# SilentStepStick_v12_5V.net
KiCad netlist of a schematic drawn in EAGLE
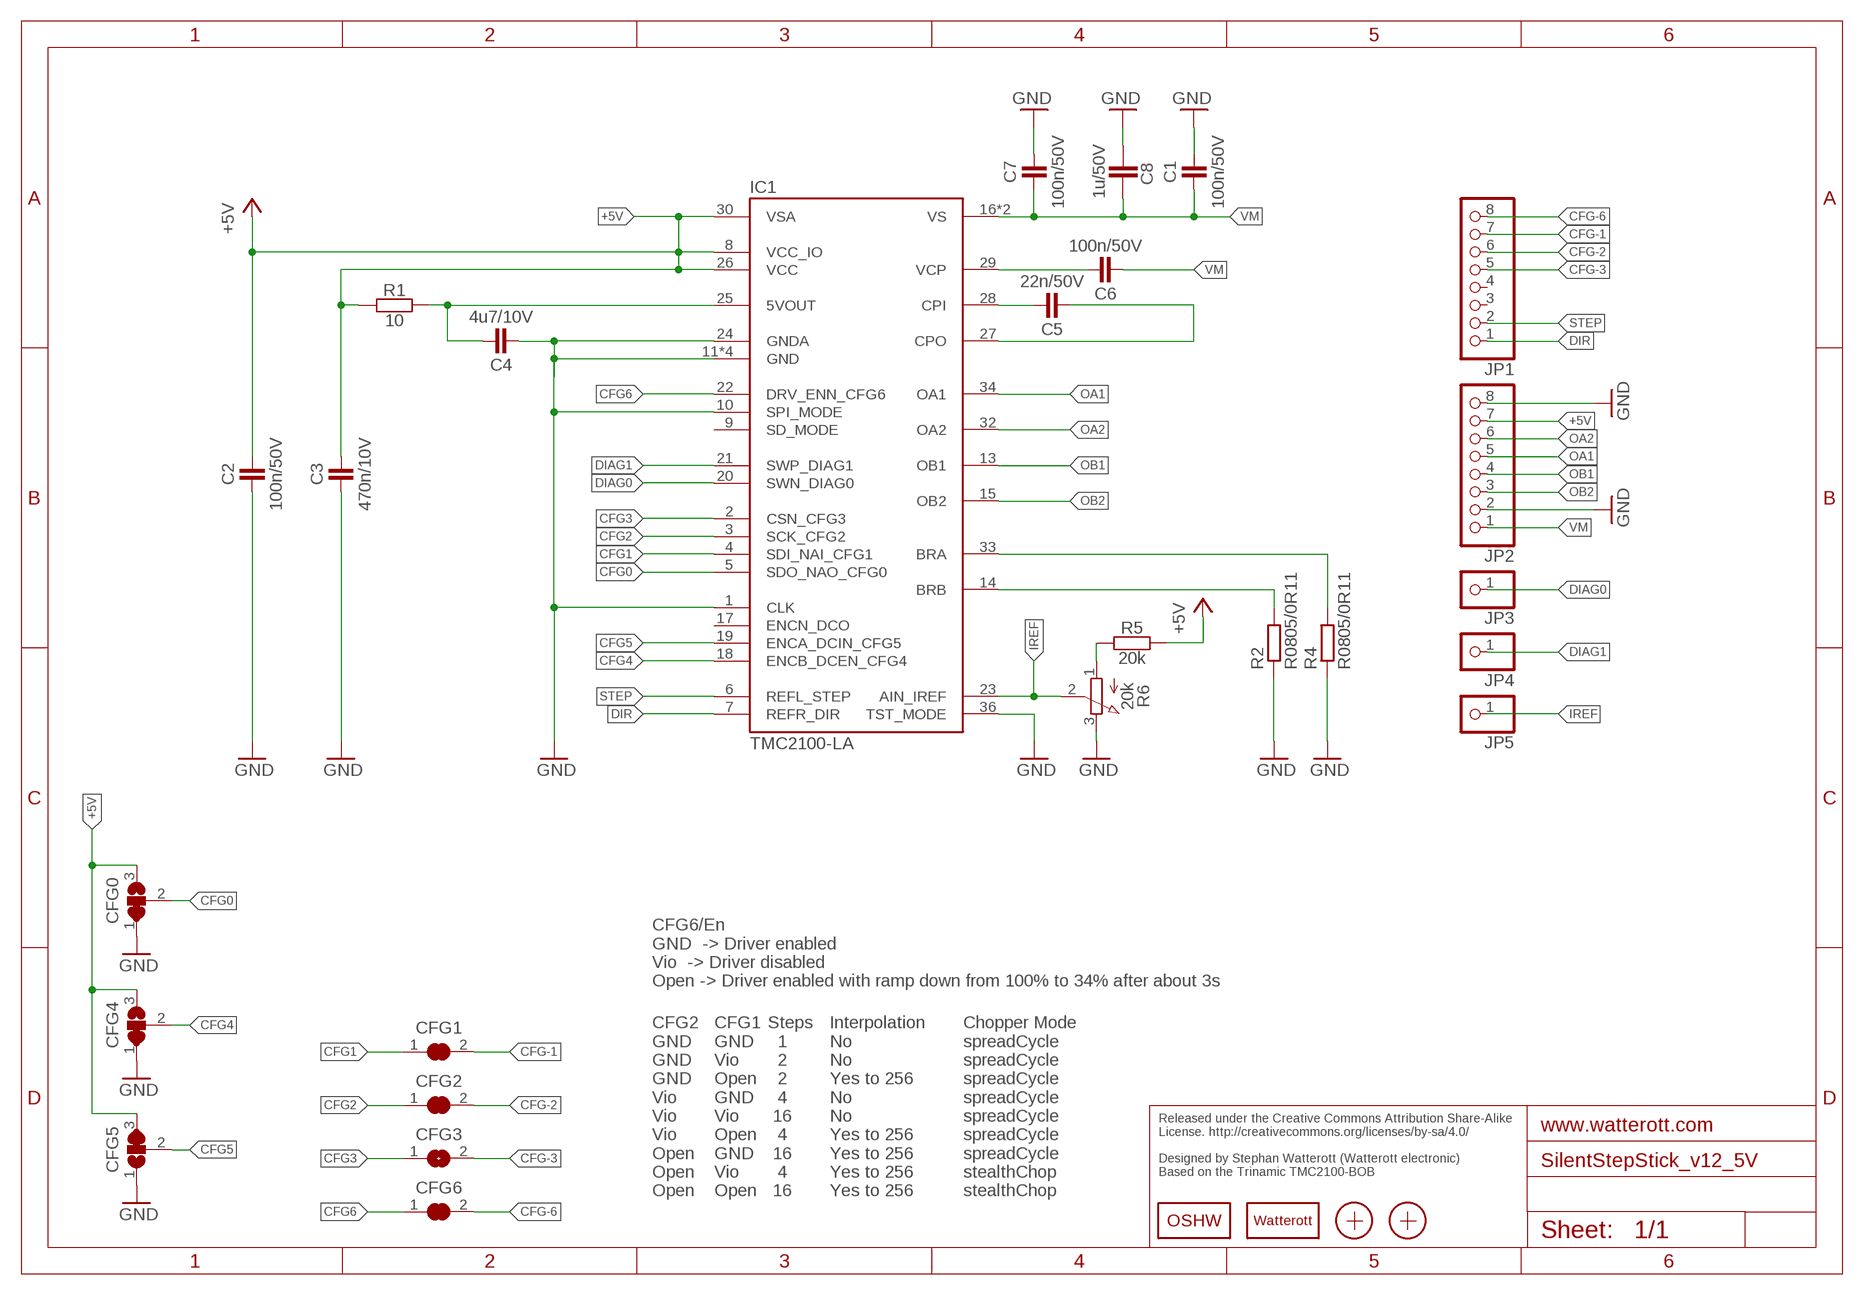
[diagram p0: schematic, sheet 1]

(export (version "E")
  (design (tool "Eeschema 10.0.6"))
  (components
    (comp (ref "C1")
      (value "100n/50V")
      (footprint "eagle-import:C0402")
      (libsource (lib "eagle-import") (part "CAPACITOR-0402"))
    )
    (comp (ref "C2")
      (value "100n/50V")
      (footprint "eagle-import:C0402")
      (libsource (lib "eagle-import") (part "CAPACITOR-0402"))
    )
    (comp (ref "C3")
      (value "470n/10V")
      (footprint "eagle-import:C0402")
      (libsource (lib "eagle-import") (part "CAPACITOR-0402"))
    )
    (comp (ref "C4")
      (value "4u7/10V")
      (footprint "eagle-import:C0402")
      (libsource (lib "eagle-import") (part "CAPACITOR-0402"))
    )
    (comp (ref "C5")
      (value "22n/50V")
      (footprint "eagle-import:C0402")
      (libsource (lib "eagle-import") (part "CAPACITOR-0402"))
    )
    (comp (ref "C6")
      (value "100n/50V")
      (footprint "eagle-import:C0402")
      (libsource (lib "eagle-import") (part "CAPACITOR-0402"))
    )
    (comp (ref "C7")
      (value "100n/50V")
      (footprint "eagle-import:C0402")
      (libsource (lib "eagle-import") (part "CAPACITOR-0402"))
    )
    (comp (ref "C8")
      (value "1u/50V")
      (footprint "eagle-import:C0603")
      (libsource (lib "eagle-import") (part "C-EUC0603"))
    )
    (comp (ref "CFG0")
      (value "JUMPER3-0201")
      (footprint "eagle-import:JUMPER3-0201")
      (libsource (lib "eagle-import") (part "JUMPER3-0201"))
    )
    (comp (ref "CFG1")
      (value "JUMPER2-0201")
      (footprint "eagle-import:JUMPER2-0201")
      (libsource (lib "eagle-import") (part "JUMPER2-0201"))
    )
    (comp (ref "CFG2")
      (value "JUMPER2-0201")
      (footprint "eagle-import:JUMPER2-0201")
      (libsource (lib "eagle-import") (part "JUMPER2-0201"))
    )
    (comp (ref "CFG3")
      (value "JUMPER2-0201")
      (footprint "eagle-import:JUMPER2-0201")
      (libsource (lib "eagle-import") (part "JUMPER2-0201"))
    )
    (comp (ref "CFG4")
      (value "JUMPER3-0201")
      (footprint "eagle-import:JUMPER3-0201")
      (libsource (lib "eagle-import") (part "JUMPER3-0201"))
    )
    (comp (ref "CFG5")
      (value "JUMPER3-0201")
      (footprint "eagle-import:JUMPER3-0201")
      (libsource (lib "eagle-import") (part "JUMPER3-0201"))
    )
    (comp (ref "CFG6")
      (value "JUMPER2-0201")
      (footprint "eagle-import:JUMPER2-0201")
      (libsource (lib "eagle-import") (part "JUMPER2-0201"))
    )
    (comp (ref "IC1")
      (value "TMC2100-LA")
      (footprint "eagle-import:QFN36-PAD")
      (libsource (lib "eagle-import") (part "TMC2100-LA"))
    )
    (comp (ref "JP1")
      (value "PINHD-1X08_2.54-S")
      (footprint "eagle-import:1X08-S")
      (libsource (lib "eagle-import") (part "PINHD-1X08_2.54-S"))
    )
    (comp (ref "JP2")
      (value "PINHD-1X08_2.54-S")
      (footprint "eagle-import:1X08-S")
      (libsource (lib "eagle-import") (part "PINHD-1X08_2.54-S"))
    )
    (comp (ref "JP3")
      (value "PINHD-1X1")
      (footprint "eagle-import:1X01")
      (libsource (lib "eagle-import") (part "PINHD-1X1"))
    )
    (comp (ref "JP4")
      (value "PINHD-1X1")
      (footprint "eagle-import:1X01")
      (libsource (lib "eagle-import") (part "PINHD-1X1"))
    )
    (comp (ref "JP5")
      (value "PINHD-1X1")
      (footprint "eagle-import:1X01")
      (libsource (lib "eagle-import") (part "PINHD-1X1"))
    )
    (comp (ref "LOGO1")
      (value "OSHW_LOGOX0070")
      (footprint "eagle-import:OSHW_6X70")
      (libsource (lib "eagle-import") (part "OSHW_LOGOX0070"))
    )
    (comp (ref "LOGO2")
      (value "LOGO-S_PLACE_M")
      (footprint "eagle-import:SPARK_TPLACE_M")
      (libsource (lib "eagle-import") (part "LOGO-S_PLACE_M"))
    )
    (comp (ref "R1")
      (value "10")
      (footprint "eagle-import:C0402")
      (libsource (lib "eagle-import") (part "RESISTOR-0402"))
    )
    (comp (ref "R2")
      (value "R0805/0R11")
      (footprint "eagle-import:M0805")
      (libsource (lib "eagle-import") (part "R-EU_M0805"))
    )
    (comp (ref "R4")
      (value "R0805/0R11")
      (footprint "eagle-import:M0805")
      (libsource (lib "eagle-import") (part "R-EU_M0805"))
    )
    (comp (ref "R5")
      (value "20k")
      (footprint "eagle-import:C0402")
      (libsource (lib "eagle-import") (part "RESISTOR-0402"))
    )
    (comp (ref "R6")
      (value "20k")
      (footprint "eagle-import:POT_EVM3R")
      (libsource (lib "eagle-import") (part "POTEVM3R"))
    )
    (comp (ref "X1")
      (value "PASSER-07")
      (footprint "eagle-import:PASSER_07MM")
      (libsource (lib "eagle-import") (part "PASSER-07"))
    )
    (comp (ref "X2")
      (value "PASSER-07")
      (footprint "eagle-import:PASSER_07MM")
      (libsource (lib "eagle-import") (part "PASSER-07"))
    )
  )
  (nets
    (net (code "1") (name "+5V") (class "Default")
      (node (ref "C2") (pin "2") (pinfunction "2_2") (pintype "passive"))
      (node (ref "C3") (pin "2") (pinfunction "2_2") (pintype "passive"))
      (node (ref "CFG0") (pin "3") (pinfunction "3_3") (pintype "passive"))
      (node (ref "CFG4") (pin "3") (pinfunction "3_3") (pintype "passive"))
      (node (ref "CFG5") (pin "3") (pinfunction "3_3") (pintype "passive"))
      (node (ref "IC1") (pin "26") (pinfunction "VCC_26") (pintype "power_in"))
      (node (ref "IC1") (pin "30") (pinfunction "VSA_30") (pintype "power_in"))
      (node (ref "IC1") (pin "8") (pinfunction "VCC_IO_8") (pintype "power_in"))
      (node (ref "JP2") (pin "7") (pinfunction "7_7") (pintype "passive"))
      (node (ref "R1") (pin "1") (pinfunction "1_1") (pintype "passive"))
      (node (ref "R5") (pin "2") (pinfunction "2_2") (pintype "passive"))
    )
    (net (code "2") (name "CFG-1") (class "Default")
      (node (ref "CFG1") (pin "2") (pinfunction "2_2") (pintype "passive"))
      (node (ref "JP1") (pin "7") (pinfunction "7_7") (pintype "passive"))
    )
    (net (code "3") (name "CFG-2") (class "Default")
      (node (ref "CFG2") (pin "2") (pinfunction "2_2") (pintype "passive"))
      (node (ref "JP1") (pin "6") (pinfunction "6_6") (pintype "passive"))
    )
    (net (code "4") (name "CFG-3") (class "Default")
      (node (ref "CFG3") (pin "2") (pinfunction "2_2") (pintype "passive"))
      (node (ref "JP1") (pin "5") (pinfunction "5_5") (pintype "passive"))
    )
    (net (code "5") (name "CFG-6") (class "Default")
      (node (ref "CFG6") (pin "2") (pinfunction "2_2") (pintype "passive"))
      (node (ref "JP1") (pin "8") (pinfunction "8_8") (pintype "passive"))
    )
    (net (code "6") (name "CFG0") (class "Default")
      (node (ref "CFG0") (pin "2") (pinfunction "2_2") (pintype "passive"))
      (node (ref "IC1") (pin "5") (pinfunction "SDO_NAO_CFG0_5") (pintype "bidirectional"))
    )
    (net (code "7") (name "CFG1") (class "Default")
      (node (ref "CFG1") (pin "1") (pinfunction "1_1") (pintype "passive"))
      (node (ref "IC1") (pin "4") (pinfunction "SDI_NAI_CFG1_4") (pintype "bidirectional"))
    )
    (net (code "8") (name "CFG2") (class "Default")
      (node (ref "CFG2") (pin "1") (pinfunction "1_1") (pintype "passive"))
      (node (ref "IC1") (pin "3") (pinfunction "SCK_CFG2_3") (pintype "bidirectional"))
    )
    (net (code "9") (name "CFG3") (class "Default")
      (node (ref "CFG3") (pin "1") (pinfunction "1_1") (pintype "passive"))
      (node (ref "IC1") (pin "2") (pinfunction "CSN_CFG3_2") (pintype "bidirectional"))
    )
    (net (code "10") (name "CFG4") (class "Default")
      (node (ref "CFG4") (pin "2") (pinfunction "2_2") (pintype "passive"))
      (node (ref "IC1") (pin "18") (pinfunction "ENCB_DCEN_CFG4_18") (pintype "bidirectional"))
    )
    (net (code "11") (name "CFG5") (class "Default")
      (node (ref "CFG5") (pin "2") (pinfunction "2_2") (pintype "passive"))
      (node (ref "IC1") (pin "19") (pinfunction "ENCA_DCIN_CFG5_19") (pintype "bidirectional"))
    )
    (net (code "12") (name "CFG6") (class "Default")
      (node (ref "CFG6") (pin "1") (pinfunction "1_1") (pintype "passive"))
      (node (ref "IC1") (pin "22") (pinfunction "DRV_ENN_CFG6_22") (pintype "bidirectional"))
    )
    (net (code "13") (name "DIAG0") (class "Default")
      (node (ref "IC1") (pin "20") (pinfunction "SWN_DIAG0_20") (pintype "bidirectional"))
      (node (ref "JP3") (pin "1") (pinfunction "1_1") (pintype "passive"))
    )
    (net (code "14") (name "DIAG1") (class "Default")
      (node (ref "IC1") (pin "21") (pinfunction "SWP_DIAG1_21") (pintype "bidirectional"))
      (node (ref "JP4") (pin "1") (pinfunction "1_1") (pintype "passive"))
    )
    (net (code "15") (name "DIR") (class "Default")
      (node (ref "IC1") (pin "7") (pinfunction "REFR_DIR_7") (pintype "bidirectional"))
      (node (ref "JP1") (pin "1") (pinfunction "1_1") (pintype "passive"))
    )
    (net (code "16") (name "GND") (class "Default")
      (node (ref "C1") (pin "2") (pinfunction "2_2") (pintype "passive"))
      (node (ref "C2") (pin "1") (pinfunction "1_1") (pintype "passive"))
      (node (ref "C3") (pin "1") (pinfunction "1_1") (pintype "passive"))
      (node (ref "C4") (pin "1") (pinfunction "1_1") (pintype "passive"))
      (node (ref "C7") (pin "2") (pinfunction "2_2") (pintype "passive"))
      (node (ref "C8") (pin "2") (pinfunction "2_2") (pintype "passive"))
      (node (ref "CFG0") (pin "1") (pinfunction "1_1") (pintype "passive"))
      (node (ref "CFG4") (pin "1") (pinfunction "1_1") (pintype "passive"))
      (node (ref "CFG5") (pin "1") (pinfunction "1_1") (pintype "passive"))
      (node (ref "IC1") (pin "1") (pinfunction "CLK_1") (pintype "bidirectional"))
      (node (ref "IC1") (pin "10") (pinfunction "SPI_MODE_10") (pintype "bidirectional"))
      (node (ref "IC1") (pin "11") (pinfunction "GND_11") (pintype "power_in"))
      (node (ref "IC1") (pin "12") (pinfunction "GND_12") (pintype "power_in"))
      (node (ref "IC1") (pin "24") (pinfunction "GNDA_24") (pintype "power_in"))
      (node (ref "IC1") (pin "35") (pinfunction "GND_35") (pintype "power_in"))
      (node (ref "IC1") (pin "36") (pinfunction "TST_MODE_36") (pintype "bidirectional"))
      (node (ref "IC1") (pin "TP") (pinfunction "GND_TP") (pintype "power_in"))
      (node (ref "JP2") (pin "2") (pinfunction "2_2") (pintype "passive"))
      (node (ref "JP2") (pin "8") (pinfunction "8_8") (pintype "passive"))
      (node (ref "R2") (pin "1") (pinfunction "1_1") (pintype "passive"))
      (node (ref "R4") (pin "1") (pinfunction "1_1") (pintype "passive"))
      (node (ref "R6") (pin "3") (pinfunction "E_3") (pintype "passive"))
    )
    (net (code "17") (name "IREF") (class "Default")
      (node (ref "IC1") (pin "23") (pinfunction "AIN_IREF_23") (pintype "passive"))
      (node (ref "JP5") (pin "1") (pinfunction "1_1") (pintype "passive"))
      (node (ref "R6") (pin "2") (pinfunction "S_2") (pintype "passive"))
    )
    (net (code "18") (name "Net-(IC1-5VOUT)") (class "Default")
      (node (ref "C4") (pin "2") (pinfunction "2_2") (pintype "passive"))
      (node (ref "IC1") (pin "25") (pinfunction "5VOUT_25") (pintype "power_in"))
      (node (ref "R1") (pin "2") (pinfunction "2_2") (pintype "passive"))
    )
    (net (code "19") (name "Net-(IC1-BRA)") (class "Default")
      (node (ref "IC1") (pin "33") (pinfunction "BRA_33") (pintype "output"))
      (node (ref "R4") (pin "2") (pinfunction "2_2") (pintype "passive"))
    )
    (net (code "20") (name "Net-(IC1-BRB)") (class "Default")
      (node (ref "IC1") (pin "14") (pinfunction "BRB_14") (pintype "output"))
      (node (ref "R2") (pin "2") (pinfunction "2_2") (pintype "passive"))
    )
    (net (code "21") (name "Net-(IC1-CPI)") (class "Default")
      (node (ref "C5") (pin "2") (pinfunction "2_2") (pintype "passive"))
      (node (ref "IC1") (pin "28") (pinfunction "CPI_28") (pintype "passive"))
    )
    (net (code "22") (name "Net-(IC1-CPO)") (class "Default")
      (node (ref "C5") (pin "1") (pinfunction "1_1") (pintype "passive"))
      (node (ref "IC1") (pin "27") (pinfunction "CPO_27") (pintype "passive"))
    )
    (net (code "23") (name "Net-(IC1-VCP)") (class "Default")
      (node (ref "C6") (pin "2") (pinfunction "2_2") (pintype "passive"))
      (node (ref "IC1") (pin "29") (pinfunction "VCP_29") (pintype "passive"))
    )
    (net (code "24") (name "Net-(R6-A)") (class "Default")
      (node (ref "R5") (pin "1") (pinfunction "1_1") (pintype "passive"))
      (node (ref "R6") (pin "1") (pinfunction "A_1") (pintype "passive"))
    )
    (net (code "25") (name "OA1") (class "Default")
      (node (ref "IC1") (pin "34") (pinfunction "OA1_34") (pintype "output"))
      (node (ref "JP2") (pin "5") (pinfunction "5_5") (pintype "passive"))
    )
    (net (code "26") (name "OA2") (class "Default")
      (node (ref "IC1") (pin "32") (pinfunction "OA2_32") (pintype "output"))
      (node (ref "JP2") (pin "6") (pinfunction "6_6") (pintype "passive"))
    )
    (net (code "27") (name "OB1") (class "Default")
      (node (ref "IC1") (pin "13") (pinfunction "OB1_13") (pintype "output"))
      (node (ref "JP2") (pin "4") (pinfunction "4_4") (pintype "passive"))
    )
    (net (code "28") (name "OB2") (class "Default")
      (node (ref "IC1") (pin "15") (pinfunction "OB2_15") (pintype "output"))
      (node (ref "JP2") (pin "3") (pinfunction "3_3") (pintype "passive"))
    )
    (net (code "29") (name "STEP") (class "Default")
      (node (ref "IC1") (pin "6") (pinfunction "REFL_STEP_6") (pintype "bidirectional"))
      (node (ref "JP1") (pin "2") (pinfunction "2_2") (pintype "passive"))
    )
    (net (code "30") (name "VM") (class "Default")
      (node (ref "C1") (pin "1") (pinfunction "1_1") (pintype "passive"))
      (node (ref "C6") (pin "1") (pinfunction "1_1") (pintype "passive"))
      (node (ref "C7") (pin "1") (pinfunction "1_1") (pintype "passive"))
      (node (ref "C8") (pin "1") (pinfunction "1_1") (pintype "passive"))
      (node (ref "IC1") (pin "16") (pinfunction "VS_16") (pintype "power_in"))
      (node (ref "IC1") (pin "31") (pinfunction "VS_31") (pintype "power_in"))
      (node (ref "JP2") (pin "1") (pinfunction "1_1") (pintype "passive"))
    )
    (net (code "31") (name "unconnected-(IC1-ENCN_DCO-Pad17)") (class "Default")
      (node (ref "IC1") (pin "17") (pinfunction "ENCN_DCO_17") (pintype "bidirectional"))
    )
    (net (code "32") (name "unconnected-(IC1-SD_MODE-Pad9)") (class "Default")
      (node (ref "IC1") (pin "9") (pinfunction "SD_MODE_9") (pintype "bidirectional"))
    )
    (net (code "33") (name "unconnected-(JP1-Pad3)") (class "Default")
      (node (ref "JP1") (pin "3") (pinfunction "3_3") (pintype "passive"))
    )
    (net (code "34") (name "unconnected-(JP1-Pad4)") (class "Default")
      (node (ref "JP1") (pin "4") (pinfunction "4_4") (pintype "passive"))
    )
  )
)
